# Jacks_EDCPSU.net
KiCad netlist of a schematic drawn in EAGLE
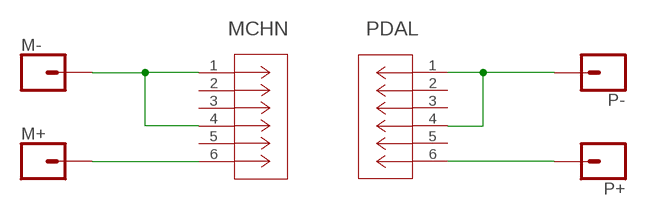
[diagram p0: schematic, sheet 1]

(export (version "E")
  (design (tool "Eeschema 10.0.6"))
  (components
    (comp (ref "M+")
      (value "CONN_01PTH_NO_SILK_KIT")
      (footprint "eagle-import:1X01NS_KIT")
      (libsource (lib "eagle-import") (part "CONN_01PTH_NO_SILK_KIT"))
    )
    (comp (ref "M-")
      (value "CONN_01PTH_NO_SILK_KIT")
      (footprint "eagle-import:1X01NS_KIT")
      (libsource (lib "eagle-import") (part "CONN_01PTH_NO_SILK_KIT"))
    )
    (comp (ref "MCHN")
      (value "ACJS-MHDR")
      (footprint "eagle-import:CONN_MHDR_AMP")
      (fields (field (name "COPYRIGHT") "Copyright (C) 2018 Accelerated Designs. All rights reserved"))
      (libsource (lib "eagle-import") (part "ACJS-MHDR"))
    )
    (comp (ref "P+")
      (value "CONN_01PTH_NO_SILK_KIT")
      (footprint "eagle-import:1X01NS_KIT")
      (libsource (lib "eagle-import") (part "CONN_01PTH_NO_SILK_KIT"))
    )
    (comp (ref "P-")
      (value "CONN_01PTH_NO_SILK_KIT")
      (footprint "eagle-import:1X01NS_KIT")
      (libsource (lib "eagle-import") (part "CONN_01PTH_NO_SILK_KIT"))
    )
    (comp (ref "PDAL")
      (value "ACJS-MHDR")
      (footprint "eagle-import:CONN_MHDR_AMP")
      (fields (field (name "COPYRIGHT") "Copyright (C) 2018 Accelerated Designs. All rights reserved"))
      (libsource (lib "eagle-import") (part "ACJS-MHDR"))
    )
  )
  (nets
    (net (code "1") (name "Net-(M+-Pad1)") (class "Default")
      (node (ref "M+") (pin "1") (pinfunction "1_1") (pintype "passive"))
      (node (ref "MCHN") (pin "6") (pinfunction "6_6") (pintype "passive"))
    )
    (net (code "2") (name "Net-(M--Pad1)") (class "Default")
      (node (ref "M-") (pin "1") (pinfunction "1_1") (pintype "passive"))
      (node (ref "MCHN") (pin "1") (pinfunction "1_1") (pintype "passive"))
      (node (ref "MCHN") (pin "4") (pinfunction "4_4") (pintype "passive"))
    )
    (net (code "3") (name "Net-(P+-Pad1)") (class "Default")
      (node (ref "P+") (pin "1") (pinfunction "1_1") (pintype "passive"))
      (node (ref "PDAL") (pin "6") (pinfunction "6_6") (pintype "passive"))
    )
    (net (code "4") (name "Net-(P--Pad1)") (class "Default")
      (node (ref "P-") (pin "1") (pinfunction "1_1") (pintype "passive"))
      (node (ref "PDAL") (pin "1") (pinfunction "1_1") (pintype "passive"))
      (node (ref "PDAL") (pin "4") (pinfunction "4_4") (pintype "passive"))
    )
    (net (code "5") (name "unconnected-(MCHN-Pad2)") (class "Default")
      (node (ref "MCHN") (pin "2") (pinfunction "2_2") (pintype "passive"))
    )
    (net (code "6") (name "unconnected-(MCHN-Pad3)") (class "Default")
      (node (ref "MCHN") (pin "3") (pinfunction "3_3") (pintype "passive"))
    )
    (net (code "7") (name "unconnected-(MCHN-Pad5)") (class "Default")
      (node (ref "MCHN") (pin "5") (pinfunction "5_5") (pintype "passive"))
    )
    (net (code "8") (name "unconnected-(PDAL-Pad2)") (class "Default")
      (node (ref "PDAL") (pin "2") (pinfunction "2_2") (pintype "passive"))
    )
    (net (code "9") (name "unconnected-(PDAL-Pad3)") (class "Default")
      (node (ref "PDAL") (pin "3") (pinfunction "3_3") (pintype "passive"))
    )
    (net (code "10") (name "unconnected-(PDAL-Pad5)") (class "Default")
      (node (ref "PDAL") (pin "5") (pinfunction "5_5") (pintype "passive"))
    )
  )
)
